# VME_connectors.net
KiCad netlist of a schematic drawn in Altium Designer
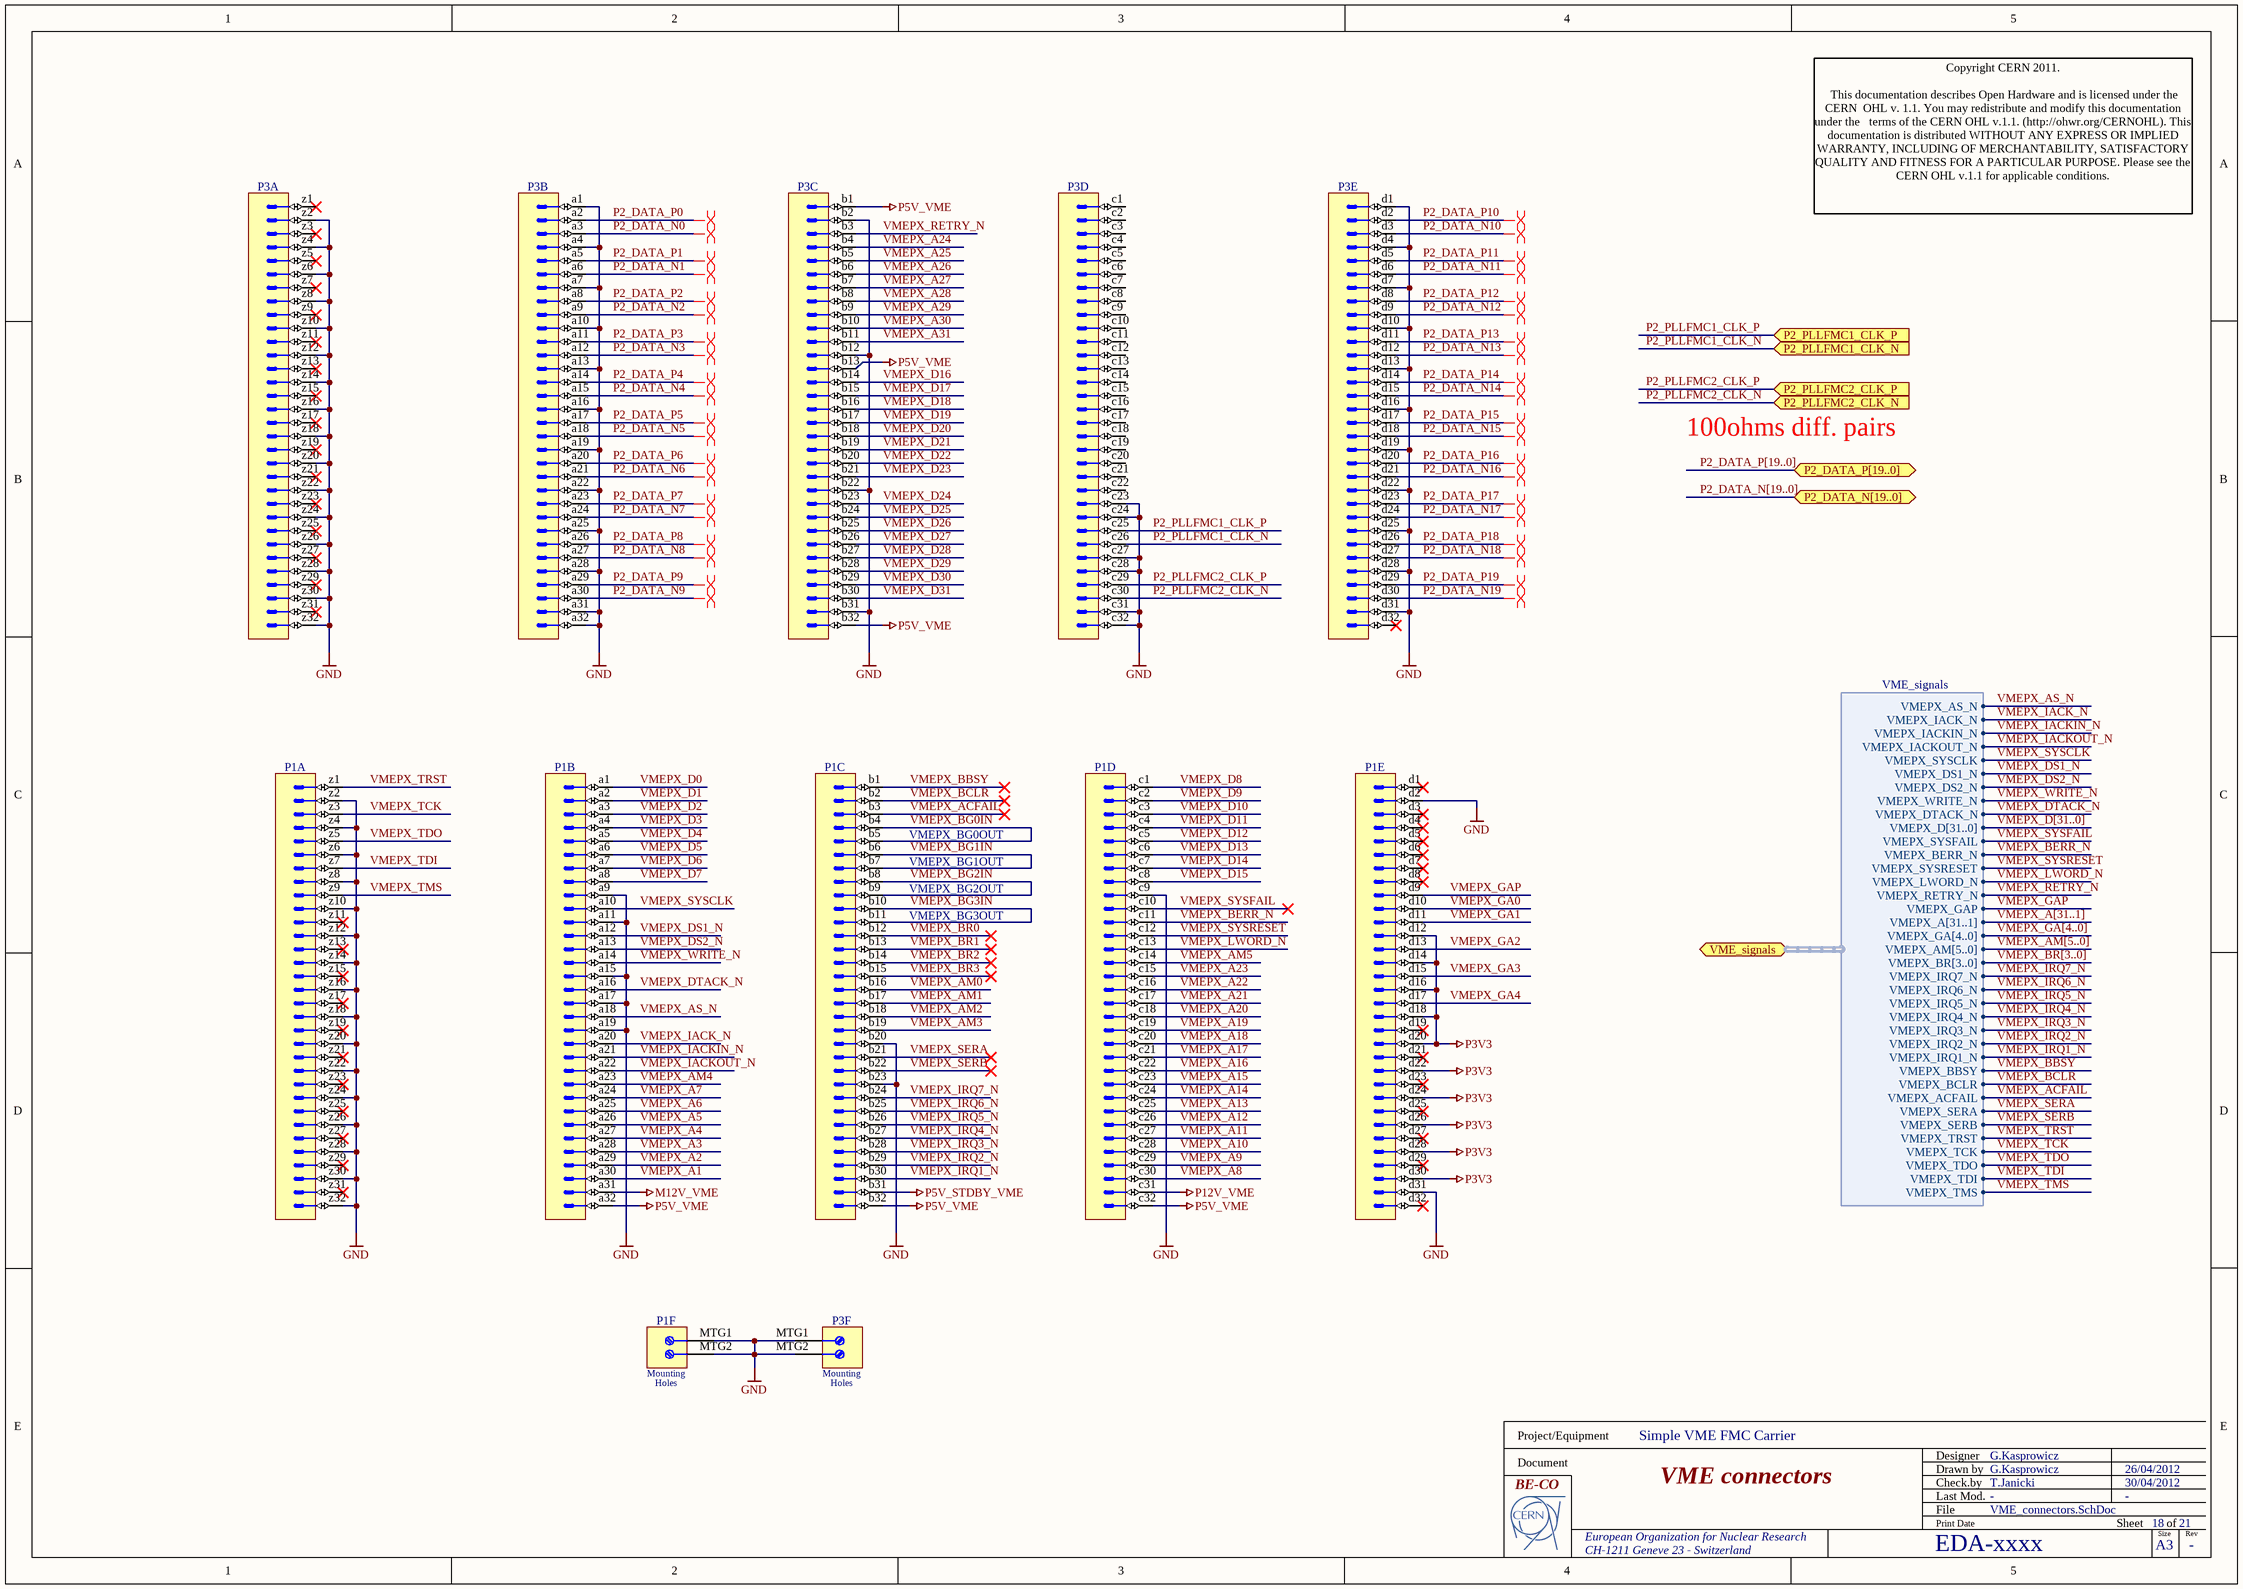
[diagram p0: VME_connectors.SchDoc]

(export (version "E")
  (design (tool "Eeschema 10.0.6"))
  (components
    (comp (ref "P1")
      (value "HAR-BUS 64")
      (footprint "HARTING_02 01 160 2101")
      (description "Connector 160zabcd Male (5x32)")
      (fields
        (field (name "PART NUMBER") "HARTING_02 01 160 2101")
        (field (name "MANUFACTURER") "HARTING")
        (field (name "AUTHOR") "CERN DEM JLC")
      )
      (libsource (lib "Connectors") (part "Connector 160zabcd Male (5x32)"))
    )
    (comp (ref "P3")
      (value "HAR-BUS 64")
      (footprint "HARTING_02 01 160 2101")
      (description "Connector 160zabcd Male (5x32)")
      (fields
        (field (name "PART NUMBER") "HARTING_02 01 160 2101")
        (field (name "MANUFACTURER") "HARTING")
        (field (name "AUTHOR") "CERN DEM JLC")
      )
      (libsource (lib "") (part "Connector 160zabcd Male (5x32)_1"))
    )
  )
  (nets
    (net (code "2") (name "/P2_DATA_N0") (class "Default")
      (node (ref "P3") (pin "a3") (pinfunction "a3_a3") (pintype "bidirectional"))
    )
    (net (code "3") (name "/P2_DATA_N1") (class "Default")
      (node (ref "P3") (pin "a6") (pinfunction "a6_a6") (pintype "bidirectional"))
    )
    (net (code "4") (name "/P2_DATA_N2") (class "Default")
      (node (ref "P3") (pin "a9") (pinfunction "a9_a9") (pintype "bidirectional"))
    )
    (net (code "5") (name "/P2_DATA_N3") (class "Default")
      (node (ref "P3") (pin "a12") (pinfunction "a12_a12") (pintype "bidirectional"))
    )
    (net (code "6") (name "/P2_DATA_N4") (class "Default")
      (node (ref "P3") (pin "a15") (pinfunction "a15_a15") (pintype "bidirectional"))
    )
    (net (code "7") (name "/P2_DATA_N5") (class "Default")
      (node (ref "P3") (pin "a18") (pinfunction "a18_a18") (pintype "bidirectional"))
    )
    (net (code "8") (name "/P2_DATA_N6") (class "Default")
      (node (ref "P3") (pin "a21") (pinfunction "a21_a21") (pintype "bidirectional"))
    )
    (net (code "9") (name "/P2_DATA_N7") (class "Default")
      (node (ref "P3") (pin "a24") (pinfunction "a24_a24") (pintype "bidirectional"))
    )
    (net (code "10") (name "/P2_DATA_N8") (class "Default")
      (node (ref "P3") (pin "a27") (pinfunction "a27_a27") (pintype "bidirectional"))
    )
    (net (code "11") (name "/P2_DATA_N9") (class "Default")
      (node (ref "P3") (pin "a30") (pinfunction "a30_a30") (pintype "bidirectional"))
    )
    (net (code "12") (name "/P2_DATA_N10") (class "Default")
      (node (ref "P3") (pin "d3") (pinfunction "d3_d3") (pintype "bidirectional"))
    )
    (net (code "13") (name "/P2_DATA_N11") (class "Default")
      (node (ref "P3") (pin "d6") (pinfunction "d6_d6") (pintype "bidirectional"))
    )
    (net (code "14") (name "/P2_DATA_N12") (class "Default")
      (node (ref "P3") (pin "d9") (pinfunction "d9_d9") (pintype "bidirectional"))
    )
    (net (code "15") (name "/P2_DATA_N13") (class "Default")
      (node (ref "P3") (pin "d12") (pinfunction "d12_d12") (pintype "bidirectional"))
    )
    (net (code "16") (name "/P2_DATA_N14") (class "Default")
      (node (ref "P3") (pin "d15") (pinfunction "d15_d15") (pintype "bidirectional"))
    )
    (net (code "17") (name "/P2_DATA_N15") (class "Default")
      (node (ref "P3") (pin "d18") (pinfunction "d18_d18") (pintype "bidirectional"))
    )
    (net (code "18") (name "/P2_DATA_N16") (class "Default")
      (node (ref "P3") (pin "d21") (pinfunction "d21_d21") (pintype "bidirectional"))
    )
    (net (code "19") (name "/P2_DATA_N17") (class "Default")
      (node (ref "P3") (pin "d24") (pinfunction "d24_d24") (pintype "bidirectional"))
    )
    (net (code "20") (name "/P2_DATA_N18") (class "Default")
      (node (ref "P3") (pin "d27") (pinfunction "d27_d27") (pintype "bidirectional"))
    )
    (net (code "21") (name "/P2_DATA_N19") (class "Default")
      (node (ref "P3") (pin "d30") (pinfunction "d30_d30") (pintype "bidirectional"))
    )
    (net (code "23") (name "/P2_DATA_P0") (class "Default")
      (node (ref "P3") (pin "a2") (pinfunction "a2_a2") (pintype "bidirectional"))
    )
    (net (code "24") (name "/P2_DATA_P1") (class "Default")
      (node (ref "P3") (pin "a5") (pinfunction "a5_a5") (pintype "bidirectional"))
    )
    (net (code "25") (name "/P2_DATA_P2") (class "Default")
      (node (ref "P3") (pin "a8") (pinfunction "a8_a8") (pintype "bidirectional"))
    )
    (net (code "26") (name "/P2_DATA_P3") (class "Default")
      (node (ref "P3") (pin "a11") (pinfunction "a11_a11") (pintype "bidirectional"))
    )
    (net (code "27") (name "/P2_DATA_P4") (class "Default")
      (node (ref "P3") (pin "a14") (pinfunction "a14_a14") (pintype "bidirectional"))
    )
    (net (code "28") (name "/P2_DATA_P5") (class "Default")
      (node (ref "P3") (pin "a17") (pinfunction "a17_a17") (pintype "bidirectional"))
    )
    (net (code "29") (name "/P2_DATA_P6") (class "Default")
      (node (ref "P3") (pin "a20") (pinfunction "a20_a20") (pintype "bidirectional"))
    )
    (net (code "30") (name "/P2_DATA_P7") (class "Default")
      (node (ref "P3") (pin "a23") (pinfunction "a23_a23") (pintype "bidirectional"))
    )
    (net (code "31") (name "/P2_DATA_P8") (class "Default")
      (node (ref "P3") (pin "a26") (pinfunction "a26_a26") (pintype "bidirectional"))
    )
    (net (code "32") (name "/P2_DATA_P9") (class "Default")
      (node (ref "P3") (pin "a29") (pinfunction "a29_a29") (pintype "bidirectional"))
    )
    (net (code "33") (name "/P2_DATA_P10") (class "Default")
      (node (ref "P3") (pin "d2") (pinfunction "d2_d2") (pintype "bidirectional"))
    )
    (net (code "34") (name "/P2_DATA_P11") (class "Default")
      (node (ref "P3") (pin "d5") (pinfunction "d5_d5") (pintype "bidirectional"))
    )
    (net (code "35") (name "/P2_DATA_P12") (class "Default")
      (node (ref "P3") (pin "d8") (pinfunction "d8_d8") (pintype "bidirectional"))
    )
    (net (code "36") (name "/P2_DATA_P13") (class "Default")
      (node (ref "P3") (pin "d11") (pinfunction "d11_d11") (pintype "bidirectional"))
    )
    (net (code "37") (name "/P2_DATA_P14") (class "Default")
      (node (ref "P3") (pin "d14") (pinfunction "d14_d14") (pintype "bidirectional"))
    )
    (net (code "38") (name "/P2_DATA_P15") (class "Default")
      (node (ref "P3") (pin "d17") (pinfunction "d17_d17") (pintype "bidirectional"))
    )
    (net (code "39") (name "/P2_DATA_P16") (class "Default")
      (node (ref "P3") (pin "d20") (pinfunction "d20_d20") (pintype "bidirectional"))
    )
    (net (code "40") (name "/P2_DATA_P17") (class "Default")
      (node (ref "P3") (pin "d23") (pinfunction "d23_d23") (pintype "bidirectional"))
    )
    (net (code "41") (name "/P2_DATA_P18") (class "Default")
      (node (ref "P3") (pin "d26") (pinfunction "d26_d26") (pintype "bidirectional"))
    )
    (net (code "42") (name "/P2_DATA_P19") (class "Default")
      (node (ref "P3") (pin "d29") (pinfunction "d29_d29") (pintype "bidirectional"))
    )
    (net (code "44") (name "/P2_PLLFMC1_CLK_N") (class "Default")
      (node (ref "P3") (pin "c26") (pinfunction "c26_c26") (pintype "bidirectional"))
    )
    (net (code "45") (name "/P2_PLLFMC1_CLK_P") (class "Default")
      (node (ref "P3") (pin "c25") (pinfunction "c25_c25") (pintype "bidirectional"))
    )
    (net (code "46") (name "/P2_PLLFMC2_CLK_N") (class "Default")
      (node (ref "P3") (pin "c30") (pinfunction "c30_c30") (pintype "bidirectional"))
    )
    (net (code "47") (name "/P2_PLLFMC2_CLK_P") (class "Default")
      (node (ref "P3") (pin "c29") (pinfunction "c29_c29") (pintype "bidirectional"))
    )
    (net (code "48") (name "/VMEPX_A1") (class "Default")
      (node (ref "P1") (pin "a30") (pinfunction "a30_a30") (pintype "bidirectional"))
    )
    (net (code "49") (name "/VMEPX_A2") (class "Default")
      (node (ref "P1") (pin "a29") (pinfunction "a29_a29") (pintype "bidirectional"))
    )
    (net (code "50") (name "/VMEPX_A3") (class "Default")
      (node (ref "P1") (pin "a28") (pinfunction "a28_a28") (pintype "bidirectional"))
    )
    (net (code "51") (name "/VMEPX_A4") (class "Default")
      (node (ref "P1") (pin "a27") (pinfunction "a27_a27") (pintype "bidirectional"))
    )
    (net (code "52") (name "/VMEPX_A5") (class "Default")
      (node (ref "P1") (pin "a26") (pinfunction "a26_a26") (pintype "bidirectional"))
    )
    (net (code "53") (name "/VMEPX_A6") (class "Default")
      (node (ref "P1") (pin "a25") (pinfunction "a25_a25") (pintype "bidirectional"))
    )
    (net (code "54") (name "/VMEPX_A7") (class "Default")
      (node (ref "P1") (pin "a24") (pinfunction "a24_a24") (pintype "bidirectional"))
    )
    (net (code "55") (name "/VMEPX_A8") (class "Default")
      (node (ref "P1") (pin "c30") (pinfunction "c30_c30") (pintype "bidirectional"))
    )
    (net (code "56") (name "/VMEPX_A9") (class "Default")
      (node (ref "P1") (pin "c29") (pinfunction "c29_c29") (pintype "bidirectional"))
    )
    (net (code "57") (name "/VMEPX_A10") (class "Default")
      (node (ref "P1") (pin "c28") (pinfunction "c28_c28") (pintype "bidirectional"))
    )
    (net (code "58") (name "/VMEPX_A11") (class "Default")
      (node (ref "P1") (pin "c27") (pinfunction "c27_c27") (pintype "bidirectional"))
    )
    (net (code "59") (name "/VMEPX_A12") (class "Default")
      (node (ref "P1") (pin "c26") (pinfunction "c26_c26") (pintype "bidirectional"))
    )
    (net (code "60") (name "/VMEPX_A13") (class "Default")
      (node (ref "P1") (pin "c25") (pinfunction "c25_c25") (pintype "bidirectional"))
    )
    (net (code "61") (name "/VMEPX_A14") (class "Default")
      (node (ref "P1") (pin "c24") (pinfunction "c24_c24") (pintype "bidirectional"))
    )
    (net (code "62") (name "/VMEPX_A15") (class "Default")
      (node (ref "P1") (pin "c23") (pinfunction "c23_c23") (pintype "bidirectional"))
    )
    (net (code "63") (name "/VMEPX_A16") (class "Default")
      (node (ref "P1") (pin "c22") (pinfunction "c22_c22") (pintype "bidirectional"))
    )
    (net (code "64") (name "/VMEPX_A17") (class "Default")
      (node (ref "P1") (pin "c21") (pinfunction "c21_c21") (pintype "bidirectional"))
    )
    (net (code "65") (name "/VMEPX_A18") (class "Default")
      (node (ref "P1") (pin "c20") (pinfunction "c20_c20") (pintype "bidirectional"))
    )
    (net (code "66") (name "/VMEPX_A19") (class "Default")
      (node (ref "P1") (pin "c19") (pinfunction "c19_c19") (pintype "bidirectional"))
    )
    (net (code "67") (name "/VMEPX_A20") (class "Default")
      (node (ref "P1") (pin "c18") (pinfunction "c18_c18") (pintype "bidirectional"))
    )
    (net (code "68") (name "/VMEPX_A21") (class "Default")
      (node (ref "P1") (pin "c17") (pinfunction "c17_c17") (pintype "bidirectional"))
    )
    (net (code "69") (name "/VMEPX_A22") (class "Default")
      (node (ref "P1") (pin "c16") (pinfunction "c16_c16") (pintype "bidirectional"))
    )
    (net (code "70") (name "/VMEPX_A23") (class "Default")
      (node (ref "P1") (pin "c15") (pinfunction "c15_c15") (pintype "bidirectional"))
    )
    (net (code "71") (name "/VMEPX_A24") (class "Default")
      (node (ref "P3") (pin "b4") (pinfunction "b4_b4") (pintype "bidirectional"))
    )
    (net (code "72") (name "/VMEPX_A25") (class "Default")
      (node (ref "P3") (pin "b5") (pinfunction "b5_b5") (pintype "bidirectional"))
    )
    (net (code "73") (name "/VMEPX_A26") (class "Default")
      (node (ref "P3") (pin "b6") (pinfunction "b6_b6") (pintype "bidirectional"))
    )
    (net (code "74") (name "/VMEPX_A27") (class "Default")
      (node (ref "P3") (pin "b7") (pinfunction "b7_b7") (pintype "bidirectional"))
    )
    (net (code "75") (name "/VMEPX_A28") (class "Default")
      (node (ref "P3") (pin "b8") (pinfunction "b8_b8") (pintype "bidirectional"))
    )
    (net (code "76") (name "/VMEPX_A29") (class "Default")
      (node (ref "P3") (pin "b9") (pinfunction "b9_b9") (pintype "bidirectional"))
    )
    (net (code "77") (name "/VMEPX_A30") (class "Default")
      (node (ref "P3") (pin "b10") (pinfunction "b10_b10") (pintype "bidirectional"))
    )
    (net (code "78") (name "/VMEPX_A31") (class "Default")
      (node (ref "P3") (pin "b11") (pinfunction "b11_b11") (pintype "bidirectional"))
    )
    (net (code "79") (name "/VMEPX_ACFAIL") (class "Default")
      (node (ref "P1") (pin "b3") (pinfunction "b3_b3") (pintype "bidirectional"))
    )
    (net (code "80") (name "/VMEPX_AM0") (class "Default")
      (node (ref "P1") (pin "b16") (pinfunction "b16_b16") (pintype "bidirectional"))
    )
    (net (code "81") (name "/VMEPX_AM1") (class "Default")
      (node (ref "P1") (pin "b17") (pinfunction "b17_b17") (pintype "bidirectional"))
    )
    (net (code "82") (name "/VMEPX_AM2") (class "Default")
      (node (ref "P1") (pin "b18") (pinfunction "b18_b18") (pintype "bidirectional"))
    )
    (net (code "83") (name "/VMEPX_AM3") (class "Default")
      (node (ref "P1") (pin "b19") (pinfunction "b19_b19") (pintype "bidirectional"))
    )
    (net (code "84") (name "/VMEPX_AM4") (class "Default")
      (node (ref "P1") (pin "a23") (pinfunction "a23_a23") (pintype "bidirectional"))
    )
    (net (code "85") (name "/VMEPX_AM5") (class "Default")
      (node (ref "P1") (pin "c14") (pinfunction "c14_c14") (pintype "bidirectional"))
    )
    (net (code "87") (name "/VMEPX_AS_N") (class "Default")
      (node (ref "P1") (pin "a18") (pinfunction "a18_a18") (pintype "bidirectional"))
    )
    (net (code "89") (name "/VMEPX_BBSY") (class "Default")
      (node (ref "P1") (pin "b1") (pinfunction "b1_b1") (pintype "bidirectional"))
    )
    (net (code "90") (name "/VMEPX_BCLR") (class "Default")
      (node (ref "P1") (pin "b2") (pinfunction "b2_b2") (pintype "bidirectional"))
    )
    (net (code "91") (name "/VMEPX_BERR_N") (class "Default")
      (node (ref "P1") (pin "c11") (pinfunction "c11_c11") (pintype "bidirectional"))
    )
    (net (code "92") (name "/VMEPX_BG0IN") (class "Default")
      (node (ref "P1") (pin "b4") (pinfunction "b4_b4") (pintype "bidirectional"))
      (node (ref "P1") (pin "b5") (pinfunction "b5_b5") (pintype "bidirectional"))
    )
    (net (code "93") (name "/VMEPX_BG1IN") (class "Default")
      (node (ref "P1") (pin "b6") (pinfunction "b6_b6") (pintype "bidirectional"))
      (node (ref "P1") (pin "b7") (pinfunction "b7_b7") (pintype "bidirectional"))
    )
    (net (code "94") (name "/VMEPX_BG2IN") (class "Default")
      (node (ref "P1") (pin "b8") (pinfunction "b8_b8") (pintype "bidirectional"))
      (node (ref "P1") (pin "b9") (pinfunction "b9_b9") (pintype "bidirectional"))
    )
    (net (code "95") (name "/VMEPX_BG3IN") (class "Default")
      (node (ref "P1") (pin "b10") (pinfunction "b10_b10") (pintype "bidirectional"))
      (node (ref "P1") (pin "b11") (pinfunction "b11_b11") (pintype "bidirectional"))
    )
    (net (code "96") (name "/VMEPX_BR0") (class "Default")
      (node (ref "P1") (pin "b12") (pinfunction "b12_b12") (pintype "bidirectional+no_connect"))
    )
    (net (code "97") (name "/VMEPX_BR1") (class "Default")
      (node (ref "P1") (pin "b13") (pinfunction "b13_b13") (pintype "bidirectional+no_connect"))
    )
    (net (code "98") (name "/VMEPX_BR2") (class "Default")
      (node (ref "P1") (pin "b14") (pinfunction "b14_b14") (pintype "bidirectional+no_connect"))
    )
    (net (code "99") (name "/VMEPX_BR3") (class "Default")
      (node (ref "P1") (pin "b15") (pinfunction "b15_b15") (pintype "bidirectional+no_connect"))
    )
    (net (code "101") (name "/VMEPX_D0") (class "Default")
      (node (ref "P1") (pin "a1") (pinfunction "a1_a1") (pintype "bidirectional"))
    )
    (net (code "102") (name "/VMEPX_D1") (class "Default")
      (node (ref "P1") (pin "a2") (pinfunction "a2_a2") (pintype "bidirectional"))
    )
    (net (code "103") (name "/VMEPX_D2") (class "Default")
      (node (ref "P1") (pin "a3") (pinfunction "a3_a3") (pintype "bidirectional"))
    )
    (net (code "104") (name "/VMEPX_D3") (class "Default")
      (node (ref "P1") (pin "a4") (pinfunction "a4_a4") (pintype "bidirectional"))
    )
    (net (code "105") (name "/VMEPX_D4") (class "Default")
      (node (ref "P1") (pin "a5") (pinfunction "a5_a5") (pintype "bidirectional"))
    )
    (net (code "106") (name "/VMEPX_D5") (class "Default")
      (node (ref "P1") (pin "a6") (pinfunction "a6_a6") (pintype "bidirectional"))
    )
    (net (code "107") (name "/VMEPX_D6") (class "Default")
      (node (ref "P1") (pin "a7") (pinfunction "a7_a7") (pintype "bidirectional"))
    )
    (net (code "108") (name "/VMEPX_D7") (class "Default")
      (node (ref "P1") (pin "a8") (pinfunction "a8_a8") (pintype "bidirectional"))
    )
    (net (code "109") (name "/VMEPX_D8") (class "Default")
      (node (ref "P1") (pin "c1") (pinfunction "c1_c1") (pintype "bidirectional"))
    )
    (net (code "110") (name "/VMEPX_D9") (class "Default")
      (node (ref "P1") (pin "c2") (pinfunction "c2_c2") (pintype "bidirectional"))
    )
    (net (code "111") (name "/VMEPX_D10") (class "Default")
      (node (ref "P1") (pin "c3") (pinfunction "c3_c3") (pintype "bidirectional"))
    )
    (net (code "112") (name "/VMEPX_D11") (class "Default")
      (node (ref "P1") (pin "c4") (pinfunction "c4_c4") (pintype "bidirectional"))
    )
    (net (code "113") (name "/VMEPX_D12") (class "Default")
      (node (ref "P1") (pin "c5") (pinfunction "c5_c5") (pintype "bidirectional"))
    )
    (net (code "114") (name "/VMEPX_D13") (class "Default")
      (node (ref "P1") (pin "c6") (pinfunction "c6_c6") (pintype "bidirectional"))
    )
    (net (code "115") (name "/VMEPX_D14") (class "Default")
      (node (ref "P1") (pin "c7") (pinfunction "c7_c7") (pintype "bidirectional"))
    )
    (net (code "116") (name "/VMEPX_D15") (class "Default")
      (node (ref "P1") (pin "c8") (pinfunction "c8_c8") (pintype "bidirectional"))
    )
    (net (code "117") (name "/VMEPX_D16") (class "Default")
      (node (ref "P3") (pin "b14") (pinfunction "b14_b14") (pintype "bidirectional"))
    )
    (net (code "118") (name "/VMEPX_D17") (class "Default")
      (node (ref "P3") (pin "b15") (pinfunction "b15_b15") (pintype "bidirectional"))
    )
    (net (code "119") (name "/VMEPX_D18") (class "Default")
      (node (ref "P3") (pin "b16") (pinfunction "b16_b16") (pintype "bidirectional"))
    )
    (net (code "120") (name "/VMEPX_D19") (class "Default")
      (node (ref "P3") (pin "b17") (pinfunction "b17_b17") (pintype "bidirectional"))
    )
    (net (code "121") (name "/VMEPX_D20") (class "Default")
      (node (ref "P3") (pin "b18") (pinfunction "b18_b18") (pintype "bidirectional"))
    )
    (net (code "122") (name "/VMEPX_D21") (class "Default")
      (node (ref "P3") (pin "b19") (pinfunction "b19_b19") (pintype "bidirectional"))
    )
    (net (code "123") (name "/VMEPX_D22") (class "Default")
      (node (ref "P3") (pin "b20") (pinfunction "b20_b20") (pintype "bidirectional"))
    )
    (net (code "124") (name "/VMEPX_D23") (class "Default")
      (node (ref "P3") (pin "b21") (pinfunction "b21_b21") (pintype "bidirectional"))
    )
    (net (code "125") (name "/VMEPX_D24") (class "Default")
      (node (ref "P3") (pin "b23") (pinfunction "b23_b23") (pintype "bidirectional"))
    )
    (net (code "126") (name "/VMEPX_D25") (class "Default")
      (node (ref "P3") (pin "b24") (pinfunction "b24_b24") (pintype "bidirectional"))
    )
    (net (code "127") (name "/VMEPX_D26") (class "Default")
      (node (ref "P3") (pin "b25") (pinfunction "b25_b25") (pintype "bidirectional"))
    )
    (net (code "128") (name "/VMEPX_D27") (class "Default")
      (node (ref "P3") (pin "b26") (pinfunction "b26_b26") (pintype "bidirectional"))
    )
    (net (code "129") (name "/VMEPX_D28") (class "Default")
      (node (ref "P3") (pin "b27") (pinfunction "b27_b27") (pintype "bidirectional"))
    )
    (net (code "130") (name "/VMEPX_D29") (class "Default")
      (node (ref "P3") (pin "b28") (pinfunction "b28_b28") (pintype "bidirectional"))
    )
    (net (code "131") (name "/VMEPX_D30") (class "Default")
      (node (ref "P3") (pin "b29") (pinfunction "b29_b29") (pintype "bidirectional"))
    )
    (net (code "132") (name "/VMEPX_D31") (class "Default")
      (node (ref "P3") (pin "b30") (pinfunction "b30_b30") (pintype "bidirectional"))
    )
    (net (code "133") (name "/VMEPX_DS1_N") (class "Default")
      (node (ref "P1") (pin "a12") (pinfunction "a12_a12") (pintype "bidirectional"))
    )
    (net (code "134") (name "/VMEPX_DS2_N") (class "Default")
      (node (ref "P1") (pin "a13") (pinfunction "a13_a13") (pintype "bidirectional"))
    )
    (net (code "135") (name "/VMEPX_DTACK_N") (class "Default")
      (node (ref "P1") (pin "a16") (pinfunction "a16_a16") (pintype "bidirectional"))
    )
    (net (code "137") (name "/VMEPX_GA0") (class "Default")
      (node (ref "P1") (pin "d10") (pinfunction "d10_d10") (pintype "bidirectional"))
    )
    (net (code "138") (name "/VMEPX_GA1") (class "Default")
      (node (ref "P1") (pin "d11") (pinfunction "d11_d11") (pintype "bidirectional"))
    )
    (net (code "139") (name "/VMEPX_GA2") (class "Default")
      (node (ref "P1") (pin "d13") (pinfunction "d13_d13") (pintype "bidirectional"))
    )
    (net (code "140") (name "/VMEPX_GA3") (class "Default")
      (node (ref "P1") (pin "d15") (pinfunction "d15_d15") (pintype "bidirectional"))
    )
    (net (code "141") (name "/VMEPX_GA4") (class "Default")
      (node (ref "P1") (pin "d17") (pinfunction "d17_d17") (pintype "bidirectional"))
    )
    (net (code "142") (name "/VMEPX_GAP") (class "Default")
      (node (ref "P1") (pin "d9") (pinfunction "d9_d9") (pintype "bidirectional"))
    )
    (net (code "144") (name "/VMEPX_IACKIN_N") (class "Default")
      (node (ref "P1") (pin "a21") (pinfunction "a21_a21") (pintype "bidirectional"))
    )
    (net (code "145") (name "/VMEPX_IACKOUT_N") (class "Default")
      (node (ref "P1") (pin "a22") (pinfunction "a22_a22") (pintype "bidirectional"))
    )
    (net (code "146") (name "/VMEPX_IACK_N") (class "Default")
      (node (ref "P1") (pin "a20") (pinfunction "a20_a20") (pintype "bidirectional"))
    )
    (net (code "147") (name "/VMEPX_IRQ1_N") (class "Default")
      (node (ref "P1") (pin "b30") (pinfunction "b30_b30") (pintype "bidirectional"))
    )
    (net (code "148") (name "/VMEPX_IRQ2_N") (class "Default")
      (node (ref "P1") (pin "b29") (pinfunction "b29_b29") (pintype "bidirectional"))
    )
    (net (code "149") (name "/VMEPX_IRQ3_N") (class "Default")
      (node (ref "P1") (pin "b28") (pinfunction "b28_b28") (pintype "bidirectional"))
    )
    (net (code "150") (name "/VMEPX_IRQ4_N") (class "Default")
      (node (ref "P1") (pin "b27") (pinfunction "b27_b27") (pintype "bidirectional"))
    )
    (net (code "151") (name "/VMEPX_IRQ5_N") (class "Default")
      (node (ref "P1") (pin "b26") (pinfunction "b26_b26") (pintype "bidirectional"))
    )
    (net (code "152") (name "/VMEPX_IRQ6_N") (class "Default")
      (node (ref "P1") (pin "b25") (pinfunction "b25_b25") (pintype "bidirectional"))
    )
    (net (code "153") (name "/VMEPX_IRQ7_N") (class "Default")
      (node (ref "P1") (pin "b24") (pinfunction "b24_b24") (pintype "bidirectional"))
    )
    (net (code "154") (name "/VMEPX_LWORD_N") (class "Default")
      (node (ref "P1") (pin "c13") (pinfunction "c13_c13") (pintype "bidirectional"))
    )
    (net (code "155") (name "/VMEPX_RETRY_N") (class "Default")
      (node (ref "P3") (pin "b3") (pinfunction "b3_b3") (pintype "bidirectional"))
    )
    (net (code "156") (name "/VMEPX_SERA") (class "Default")
      (node (ref "P1") (pin "b21") (pinfunction "b21_b21") (pintype "bidirectional"))
    )
    (net (code "157") (name "/VMEPX_SERB") (class "Default")
      (node (ref "P1") (pin "b22") (pinfunction "b22_b22") (pintype "bidirectional"))
    )
    (net (code "158") (name "/VMEPX_SYSCLK") (class "Default")
      (node (ref "P1") (pin "a10") (pinfunction "a10_a10") (pintype "bidirectional"))
    )
    (net (code "159") (name "/VMEPX_SYSFAIL") (class "Default")
      (node (ref "P1") (pin "c10") (pinfunction "c10_c10") (pintype "bidirectional"))
    )
    (net (code "160") (name "/VMEPX_SYSRESET") (class "Default")
      (node (ref "P1") (pin "c12") (pinfunction "c12_c12") (pintype "bidirectional"))
    )
    (net (code "161") (name "/VMEPX_TCK") (class "Default")
      (node (ref "P1") (pin "z3") (pinfunction "z3_z3") (pintype "bidirectional"))
    )
    (net (code "162") (name "/VMEPX_TDI") (class "Default")
      (node (ref "P1") (pin "z7") (pinfunction "z7_z7") (pintype "bidirectional"))
    )
    (net (code "163") (name "/VMEPX_TDO") (class "Default")
      (node (ref "P1") (pin "z5") (pinfunction "z5_z5") (pintype "bidirectional"))
    )
    (net (code "164") (name "/VMEPX_TMS") (class "Default")
      (node (ref "P1") (pin "z9") (pinfunction "z9_z9") (pintype "bidirectional"))
    )
    (net (code "165") (name "/VMEPX_TRST") (class "Default")
      (node (ref "P1") (pin "z1") (pinfunction "z1_z1") (pintype "bidirectional"))
    )
    (net (code "166") (name "/VMEPX_WRITE_N") (class "Default")
      (node (ref "P1") (pin "a14") (pinfunction "a14_a14") (pintype "bidirectional"))
    )
    (net (code "168") (name "GND") (class "Default")
      (node (ref "P1") (pin "MTG1") (pinfunction "MTG1_MTG1") (pintype "passive"))
      (node (ref "P1") (pin "MTG2") (pinfunction "MTG2_MTG2") (pintype "passive"))
      (node (ref "P1") (pin "a11") (pinfunction "a11_a11") (pintype "bidirectional"))
      (node (ref "P1") (pin "a15") (pinfunction "a15_a15") (pintype "bidirectional"))
      (node (ref "P1") (pin "a17") (pinfunction "a17_a17") (pintype "bidirectional"))
      (node (ref "P1") (pin "a19") (pinfunction "a19_a19") (pintype "bidirectional"))
      (node (ref "P1") (pin "a9") (pinfunction "a9_a9") (pintype "bidirectional"))
      (node (ref "P1") (pin "b20") (pinfunction "b20_b20") (pintype "bidirectional"))
      (node (ref "P1") (pin "b23") (pinfunction "b23_b23") (pintype "bidirectional"))
      (node (ref "P1") (pin "c9") (pinfunction "c9_c9") (pintype "bidirectional"))
      (node (ref "P1") (pin "d2") (pinfunction "d2_d2") (pintype "bidirectional"))
      (node (ref "P1") (pin "d31") (pinfunction "d31_d31") (pintype "bidirectional"))
      (node (ref "P1") (pin "z10") (pinfunction "z10_z10") (pintype "bidirectional"))
      (node (ref "P1") (pin "z12") (pinfunction "z12_z12") (pintype "bidirectional"))
      (node (ref "P1") (pin "z14") (pinfunction "z14_z14") (pintype "bidirectional"))
      (node (ref "P1") (pin "z16") (pinfunction "z16_z16") (pintype "bidirectional"))
      (node (ref "P1") (pin "z18") (pinfunction "z18_z18") (pintype "bidirectional"))
      (node (ref "P1") (pin "z2") (pinfunction "z2_z2") (pintype "bidirectional"))
      (node (ref "P1") (pin "z20") (pinfunction "z20_z20") (pintype "bidirectional"))
      (node (ref "P1") (pin "z22") (pinfunction "z22_z22") (pintype "bidirectional"))
      (node (ref "P1") (pin "z24") (pinfunction "z24_z24") (pintype "bidirectional"))
      (node (ref "P1") (pin "z26") (pinfunction "z26_z26") (pintype "bidirectional"))
      (node (ref "P1") (pin "z28") (pinfunction "z28_z28") (pintype "bidirectional"))
      (node (ref "P1") (pin "z30") (pinfunction "z30_z30") (pintype "bidirectional"))
      (node (ref "P1") (pin "z32") (pinfunction "z32_z32") (pintype "bidirectional"))
      (node (ref "P1") (pin "z4") (pinfunction "z4_z4") (pintype "bidirectional"))
      (node (ref "P1") (pin "z6") (pinfunction "z6_z6") (pintype "bidirectional"))
      (node (ref "P1") (pin "z8") (pinfunction "z8_z8") (pintype "bidirectional"))
      (node (ref "P3") (pin "MTG1") (pinfunction "MTG1_MTG1") (pintype "passive"))
      (node (ref "P3") (pin "MTG2") (pinfunction "MTG2_MTG2") (pintype "passive"))
      (node (ref "P3") (pin "a1") (pinfunction "a1_a1") (pintype "bidirectional"))
      (node (ref "P3") (pin "a10") (pinfunction "a10_a10") (pintype "bidirectional"))
      (node (ref "P3") (pin "a13") (pinfunction "a13_a13") (pintype "bidirectional"))
      (node (ref "P3") (pin "a16") (pinfunction "a16_a16") (pintype "bidirectional"))
      (node (ref "P3") (pin "a19") (pinfunction "a19_a19") (pintype "bidirectional"))
      (node (ref "P3") (pin "a22") (pinfunction "a22_a22") (pintype "bidirectional"))
      (node (ref "P3") (pin "a25") (pinfunction "a25_a25") (pintype "bidirectional"))
      (node (ref "P3") (pin "a28") (pinfunction "a28_a28") (pintype "bidirectional"))
      (node (ref "P3") (pin "a31") (pinfunction "a31_a31") (pintype "bidirectional"))
      (node (ref "P3") (pin "a32") (pinfunction "a32_a32") (pintype "bidirectional"))
      (node (ref "P3") (pin "a4") (pinfunction "a4_a4") (pintype "bidirectional"))
      (node (ref "P3") (pin "a7") (pinfunction "a7_a7") (pintype "bidirectional"))
      (node (ref "P3") (pin "b12") (pinfunction "b12_b12") (pintype "bidirectional"))
      (node (ref "P3") (pin "b2") (pinfunction "b2_b2") (pintype "bidirectional"))
      (node (ref "P3") (pin "b22") (pinfunction "b22_b22") (pintype "bidirectional"))
      (node (ref "P3") (pin "b31") (pinfunction "b31_b31") (pintype "bidirectional"))
      (node (ref "P3") (pin "c23") (pinfunction "c23_c23") (pintype "bidirectional"))
      (node (ref "P3") (pin "c24") (pinfunction "c24_c24") (pintype "bidirectional"))
      (node (ref "P3") (pin "c27") (pinfunction "c27_c27") (pintype "bidirectional"))
      (node (ref "P3") (pin "c28") (pinfunction "c28_c28") (pintype "bidirectional"))
      (node (ref "P3") (pin "c31") (pinfunction "c31_c31") (pintype "bidirectional"))
      (node (ref "P3") (pin "c32") (pinfunction "c32_c32") (pintype "bidirectional"))
      (node (ref "P3") (pin "d1") (pinfunction "d1_d1") (pintype "bidirectional"))
      (node (ref "P3") (pin "d10") (pinfunction "d10_d10") (pintype "bidirectional"))
      (node (ref "P3") (pin "d13") (pinfunction "d13_d13") (pintype "bidirectional"))
      (node (ref "P3") (pin "d16") (pinfunction "d16_d16") (pintype "bidirectional"))
      (node (ref "P3") (pin "d19") (pinfunction "d19_d19") (pintype "bidirectional"))
      (node (ref "P3") (pin "d22") (pinfunction "d22_d22") (pintype "bidirectional"))
      (node (ref "P3") (pin "d25") (pinfunction "d25_d25") (pintype "bidirectional"))
      (node (ref "P3") (pin "d28") (pinfunction "d28_d28") (pintype "bidirectional"))
      (node (ref "P3") (pin "d31") (pinfunction "d31_d31") (pintype "bidirectional"))
      (node (ref "P3") (pin "d4") (pinfunction "d4_d4") (pintype "bidirectional"))
      (node (ref "P3") (pin "d7") (pinfunction "d7_d7") (pintype "bidirectional"))
      (node (ref "P3") (pin "z10") (pinfunction "z10_z10") (pintype "bidirectional"))
      (node (ref "P3") (pin "z12") (pinfunction "z12_z12") (pintype "bidirectional"))
      (node (ref "P3") (pin "z14") (pinfunction "z14_z14") (pintype "bidirectional"))
      (node (ref "P3") (pin "z16") (pinfunction "z16_z16") (pintype "bidirectional"))
      (node (ref "P3") (pin "z18") (pinfunction "z18_z18") (pintype "bidirectional"))
      (node (ref "P3") (pin "z2") (pinfunction "z2_z2") (pintype "bidirectional"))
      (node (ref "P3") (pin "z20") (pinfunction "z20_z20") (pintype "bidirectional"))
      (node (ref "P3") (pin "z22") (pinfunction "z22_z22") (pintype "bidirectional"))
      (node (ref "P3") (pin "z24") (pinfunction "z24_z24") (pintype "bidirectional"))
      (node (ref "P3") (pin "z26") (pinfunction "z26_z26") (pintype "bidirectional"))
      (node (ref "P3") (pin "z28") (pinfunction "z28_z28") (pintype "bidirectional"))
      (node (ref "P3") (pin "z30") (pinfunction "z30_z30") (pintype "bidirectional"))
      (node (ref "P3") (pin "z32") (pinfunction "z32_z32") (pintype "bidirectional"))
      (node (ref "P3") (pin "z4") (pinfunction "z4_z4") (pintype "bidirectional"))
      (node (ref "P3") (pin "z6") (pinfunction "z6_z6") (pintype "bidirectional"))
      (node (ref "P3") (pin "z8") (pinfunction "z8_z8") (pintype "bidirectional"))
    )
    (net (code "169") (name "M12V_VME") (class "Default")
      (node (ref "P1") (pin "a31") (pinfunction "a31_a31") (pintype "bidirectional"))
    )
    (net (code "170") (name "P3V3") (class "Default")
      (node (ref "P1") (pin "d12") (pinfunction "d12_d12") (pintype "bidirectional"))
      (node (ref "P1") (pin "d14") (pinfunction "d14_d14") (pintype "bidirectional"))
      (node (ref "P1") (pin "d16") (pinfunction "d16_d16") (pintype "bidirectional"))
      (node (ref "P1") (pin "d18") (pinfunction "d18_d18") (pintype "bidirectional"))
      (node (ref "P1") (pin "d20") (pinfunction "d20_d20") (pintype "bidirectional"))
      (node (ref "P1") (pin "d22") (pinfunction "d22_d22") (pintype "bidirectional"))
      (node (ref "P1") (pin "d24") (pinfunction "d24_d24") (pintype "bidirectional"))
      (node (ref "P1") (pin "d26") (pinfunction "d26_d26") (pintype "bidirectional"))
      (node (ref "P1") (pin "d28") (pinfunction "d28_d28") (pintype "bidirectional"))
      (node (ref "P1") (pin "d30") (pinfunction "d30_d30") (pintype "bidirectional"))
    )
    (net (code "171") (name "P5V_STDBY_VME") (class "Default")
      (node (ref "P1") (pin "b31") (pinfunction "b31_b31") (pintype "bidirectional"))
    )
    (net (code "172") (name "P5V_VME") (class "Default")
      (node (ref "P1") (pin "a32") (pinfunction "a32_a32") (pintype "bidirectional"))
      (node (ref "P1") (pin "b32") (pinfunction "b32_b32") (pintype "bidirectional"))
      (node (ref "P1") (pin "c32") (pinfunction "c32_c32") (pintype "bidirectional"))
      (node (ref "P3") (pin "b1") (pinfunction "b1_b1") (pintype "bidirectional"))
      (node (ref "P3") (pin "b13") (pinfunction "b13_b13") (pintype "bidirectional"))
      (node (ref "P3") (pin "b32") (pinfunction "b32_b32") (pintype "bidirectional"))
    )
    (net (code "173") (name "P12V_VME") (class "Default")
      (node (ref "P1") (pin "c31") (pinfunction "c31_c31") (pintype "bidirectional"))
    )
    (net (code "174") (name "unconnected-(P1-Padd1)") (class "Default")
      (node (ref "P1") (pin "d1") (pinfunction "d1_d1") (pintype "bidirectional+no_connect"))
    )
    (net (code "175") (name "unconnected-(P1-Padd3)") (class "Default")
      (node (ref "P1") (pin "d3") (pinfunction "d3_d3") (pintype "bidirectional+no_connect"))
    )
    (net (code "176") (name "unconnected-(P1-Padd4)") (class "Default")
      (node (ref "P1") (pin "d4") (pinfunction "d4_d4") (pintype "bidirectional+no_connect"))
    )
    (net (code "177") (name "unconnected-(P1-Padd5)") (class "Default")
      (node (ref "P1") (pin "d5") (pinfunction "d5_d5") (pintype "bidirectional+no_connect"))
    )
    (net (code "178") (name "unconnected-(P1-Padd6)") (class "Default")
      (node (ref "P1") (pin "d6") (pinfunction "d6_d6") (pintype "bidirectional+no_connect"))
    )
    (net (code "179") (name "unconnected-(P1-Padd7)") (class "Default")
      (node (ref "P1") (pin "d7") (pinfunction "d7_d7") (pintype "bidirectional+no_connect"))
    )
    (net (code "180") (name "unconnected-(P1-Padd8)") (class "Default")
      (node (ref "P1") (pin "d8") (pinfunction "d8_d8") (pintype "bidirectional+no_connect"))
    )
    (net (code "181") (name "unconnected-(P1-Padd19)") (class "Default")
      (node (ref "P1") (pin "d19") (pinfunction "d19_d19") (pintype "bidirectional+no_connect"))
    )
    (net (code "182") (name "unconnected-(P1-Padd21)") (class "Default")
      (node (ref "P1") (pin "d21") (pinfunction "d21_d21") (pintype "bidirectional+no_connect"))
    )
    (net (code "183") (name "unconnected-(P1-Padd23)") (class "Default")
      (node (ref "P1") (pin "d23") (pinfunction "d23_d23") (pintype "bidirectional+no_connect"))
    )
    (net (code "184") (name "unconnected-(P1-Padd25)") (class "Default")
      (node (ref "P1") (pin "d25") (pinfunction "d25_d25") (pintype "bidirectional+no_connect"))
    )
    (net (code "185") (name "unconnected-(P1-Padd27)") (class "Default")
      (node (ref "P1") (pin "d27") (pinfunction "d27_d27") (pintype "bidirectional+no_connect"))
    )
    (net (code "186") (name "unconnected-(P1-Padd29)") (class "Default")
      (node (ref "P1") (pin "d29") (pinfunction "d29_d29") (pintype "bidirectional+no_connect"))
    )
    (net (code "187") (name "unconnected-(P1-Padd32)") (class "Default")
      (node (ref "P1") (pin "d32") (pinfunction "d32_d32") (pintype "bidirectional+no_connect"))
    )
    (net (code "188") (name "unconnected-(P1-Padz11)") (class "Default")
      (node (ref "P1") (pin "z11") (pinfunction "z11_z11") (pintype "bidirectional+no_connect"))
    )
    (net (code "189") (name "unconnected-(P1-Padz13)") (class "Default")
      (node (ref "P1") (pin "z13") (pinfunction "z13_z13") (pintype "bidirectional+no_connect"))
    )
    (net (code "190") (name "unconnected-(P1-Padz15)") (class "Default")
      (node (ref "P1") (pin "z15") (pinfunction "z15_z15") (pintype "bidirectional+no_connect"))
    )
    (net (code "191") (name "unconnected-(P1-Padz17)") (class "Default")
      (node (ref "P1") (pin "z17") (pinfunction "z17_z17") (pintype "bidirectional+no_connect"))
    )
    (net (code "192") (name "unconnected-(P1-Padz19)") (class "Default")
      (node (ref "P1") (pin "z19") (pinfunction "z19_z19") (pintype "bidirectional+no_connect"))
    )
    (net (code "193") (name "unconnected-(P1-Padz21)") (class "Default")
      (node (ref "P1") (pin "z21") (pinfunction "z21_z21") (pintype "bidirectional+no_connect"))
    )
    (net (code "194") (name "unconnected-(P1-Padz23)") (class "Default")
      (node (ref "P1") (pin "z23") (pinfunction "z23_z23") (pintype "bidirectional+no_connect"))
    )
    (net (code "195") (name "unconnected-(P1-Padz25)") (class "Default")
      (node (ref "P1") (pin "z25") (pinfunction "z25_z25") (pintype "bidirectional+no_connect"))
    )
    (net (code "196") (name "unconnected-(P1-Padz27)") (class "Default")
      (node (ref "P1") (pin "z27") (pinfunction "z27_z27") (pintype "bidirectional+no_connect"))
    )
    (net (code "197") (name "unconnected-(P1-Padz29)") (class "Default")
      (node (ref "P1") (pin "z29") (pinfunction "z29_z29") (pintype "bidirectional+no_connect"))
    )
    (net (code "198") (name "unconnected-(P1-Padz31)") (class "Default")
      (node (ref "P1") (pin "z31") (pinfunction "z31_z31") (pintype "bidirectional+no_connect"))
    )
    (net (code "199") (name "unconnected-(P3-Padc1)") (class "Default")
      (node (ref "P3") (pin "c1") (pinfunction "c1_c1") (pintype "bidirectional"))
    )
    (net (code "200") (name "unconnected-(P3-Padc2)") (class "Default")
      (node (ref "P3") (pin "c2") (pinfunction "c2_c2") (pintype "bidirectional"))
    )
    (net (code "201") (name "unconnected-(P3-Padc3)") (class "Default")
      (node (ref "P3") (pin "c3") (pinfunction "c3_c3") (pintype "bidirectional"))
    )
    (net (code "202") (name "unconnected-(P3-Padc4)") (class "Default")
      (node (ref "P3") (pin "c4") (pinfunction "c4_c4") (pintype "bidirectional"))
    )
    (net (code "203") (name "unconnected-(P3-Padc5)") (class "Default")
      (node (ref "P3") (pin "c5") (pinfunction "c5_c5") (pintype "bidirectional"))
    )
    (net (code "204") (name "unconnected-(P3-Padc6)") (class "Default")
      (node (ref "P3") (pin "c6") (pinfunction "c6_c6") (pintype "bidirectional"))
    )
    (net (code "205") (name "unconnected-(P3-Padc7)") (class "Default")
      (node (ref "P3") (pin "c7") (pinfunction "c7_c7") (pintype "bidirectional"))
    )
    (net (code "206") (name "unconnected-(P3-Padc8)") (class "Default")
      (node (ref "P3") (pin "c8") (pinfunction "c8_c8") (pintype "bidirectional"))
    )
    (net (code "207") (name "unconnected-(P3-Padc9)") (class "Default")
      (node (ref "P3") (pin "c9") (pinfunction "c9_c9") (pintype "bidirectional"))
    )
    (net (code "208") (name "unconnected-(P3-Padc10)") (class "Default")
      (node (ref "P3") (pin "c10") (pinfunction "c10_c10") (pintype "bidirectional"))
    )
    (net (code "209") (name "unconnected-(P3-Padc11)") (class "Default")
      (node (ref "P3") (pin "c11") (pinfunction "c11_c11") (pintype "bidirectional"))
    )
    (net (code "210") (name "unconnected-(P3-Padc12)") (class "Default")
      (node (ref "P3") (pin "c12") (pinfunction "c12_c12") (pintype "bidirectional"))
    )
    (net (code "211") (name "unconnected-(P3-Padc13)") (class "Default")
      (node (ref "P3") (pin "c13") (pinfunction "c13_c13") (pintype "bidirectional"))
    )
    (net (code "212") (name "unconnected-(P3-Padc14)") (class "Default")
      (node (ref "P3") (pin "c14") (pinfunction "c14_c14") (pintype "bidirectional"))
    )
    (net (code "213") (name "unconnected-(P3-Padc15)") (class "Default")
      (node (ref "P3") (pin "c15") (pinfunction "c15_c15") (pintype "bidirectional"))
    )
    (net (code "214") (name "unconnected-(P3-Padc16)") (class "Default")
      (node (ref "P3") (pin "c16") (pinfunction "c16_c16") (pintype "bidirectional"))
    )
    (net (code "215") (name "unconnected-(P3-Padc17)") (class "Default")
      (node (ref "P3") (pin "c17") (pinfunction "c17_c17") (pintype "bidirectional"))
    )
    (net (code "216") (name "unconnected-(P3-Padc18)") (class "Default")
      (node (ref "P3") (pin "c18") (pinfunction "c18_c18") (pintype "bidirectional"))
    )
    (net (code "217") (name "unconnected-(P3-Padc19)") (class "Default")
      (node (ref "P3") (pin "c19") (pinfunction "c19_c19") (pintype "bidirectional"))
    )
    (net (code "218") (name "unconnected-(P3-Padc20)") (class "Default")
      (node (ref "P3") (pin "c20") (pinfunction "c20_c20") (pintype "bidirectional"))
    )
    (net (code "219") (name "unconnected-(P3-Padc21)") (class "Default")
      (node (ref "P3") (pin "c21") (pinfunction "c21_c21") (pintype "bidirectional"))
    )
    (net (code "220") (name "unconnected-(P3-Padc22)") (class "Default")
      (node (ref "P3") (pin "c22") (pinfunction "c22_c22") (pintype "bidirectional"))
    )
    (net (code "221") (name "unconnected-(P3-Padd32)") (class "Default")
      (node (ref "P3") (pin "d32") (pinfunction "d32_d32") (pintype "bidirectional+no_connect"))
    )
    (net (code "222") (name "unconnected-(P3-Padz1)") (class "Default")
      (node (ref "P3") (pin "z1") (pinfunction "z1_z1") (pintype "bidirectional+no_connect"))
    )
    (net (code "223") (name "unconnected-(P3-Padz3)") (class "Default")
      (node (ref "P3") (pin "z3") (pinfunction "z3_z3") (pintype "bidirectional+no_connect"))
    )
    (net (code "224") (name "unconnected-(P3-Padz5)") (class "Default")
      (node (ref "P3") (pin "z5") (pinfunction "z5_z5") (pintype "bidirectional+no_connect"))
    )
    (net (code "225") (name "unconnected-(P3-Padz7)") (class "Default")
      (node (ref "P3") (pin "z7") (pinfunction "z7_z7") (pintype "bidirectional+no_connect"))
    )
    (net (code "226") (name "unconnected-(P3-Padz9)") (class "Default")
      (node (ref "P3") (pin "z9") (pinfunction "z9_z9") (pintype "bidirectional+no_connect"))
    )
    (net (code "227") (name "unconnected-(P3-Padz11)") (class "Default")
      (node (ref "P3") (pin "z11") (pinfunction "z11_z11") (pintype "bidirectional+no_connect"))
    )
    (net (code "228") (name "unconnected-(P3-Padz13)") (class "Default")
      (node (ref "P3") (pin "z13") (pinfunction "z13_z13") (pintype "bidirectional+no_connect"))
    )
    (net (code "229") (name "unconnected-(P3-Padz15)") (class "Default")
      (node (ref "P3") (pin "z15") (pinfunction "z15_z15") (pintype "bidirectional+no_connect"))
    )
    (net (code "230") (name "unconnected-(P3-Padz17)") (class "Default")
      (node (ref "P3") (pin "z17") (pinfunction "z17_z17") (pintype "bidirectional+no_connect"))
    )
    (net (code "231") (name "unconnected-(P3-Padz19)") (class "Default")
      (node (ref "P3") (pin "z19") (pinfunction "z19_z19") (pintype "bidirectional+no_connect"))
    )
    (net (code "232") (name "unconnected-(P3-Padz21)") (class "Default")
      (node (ref "P3") (pin "z21") (pinfunction "z21_z21") (pintype "bidirectional+no_connect"))
    )
    (net (code "233") (name "unconnected-(P3-Padz23)") (class "Default")
      (node (ref "P3") (pin "z23") (pinfunction "z23_z23") (pintype "bidirectional+no_connect"))
    )
    (net (code "234") (name "unconnected-(P3-Padz25)") (class "Default")
      (node (ref "P3") (pin "z25") (pinfunction "z25_z25") (pintype "bidirectional+no_connect"))
    )
    (net (code "235") (name "unconnected-(P3-Padz27)") (class "Default")
      (node (ref "P3") (pin "z27") (pinfunction "z27_z27") (pintype "bidirectional+no_connect"))
    )
    (net (code "236") (name "unconnected-(P3-Padz29)") (class "Default")
      (node (ref "P3") (pin "z29") (pinfunction "z29_z29") (pintype "bidirectional+no_connect"))
    )
    (net (code "237") (name "unconnected-(P3-Padz31)") (class "Default")
      (node (ref "P3") (pin "z31") (pinfunction "z31_z31") (pintype "bidirectional+no_connect"))
    )
  )
)
